# Sheet1.net
KiCad netlist of a schematic drawn in Altium Designer
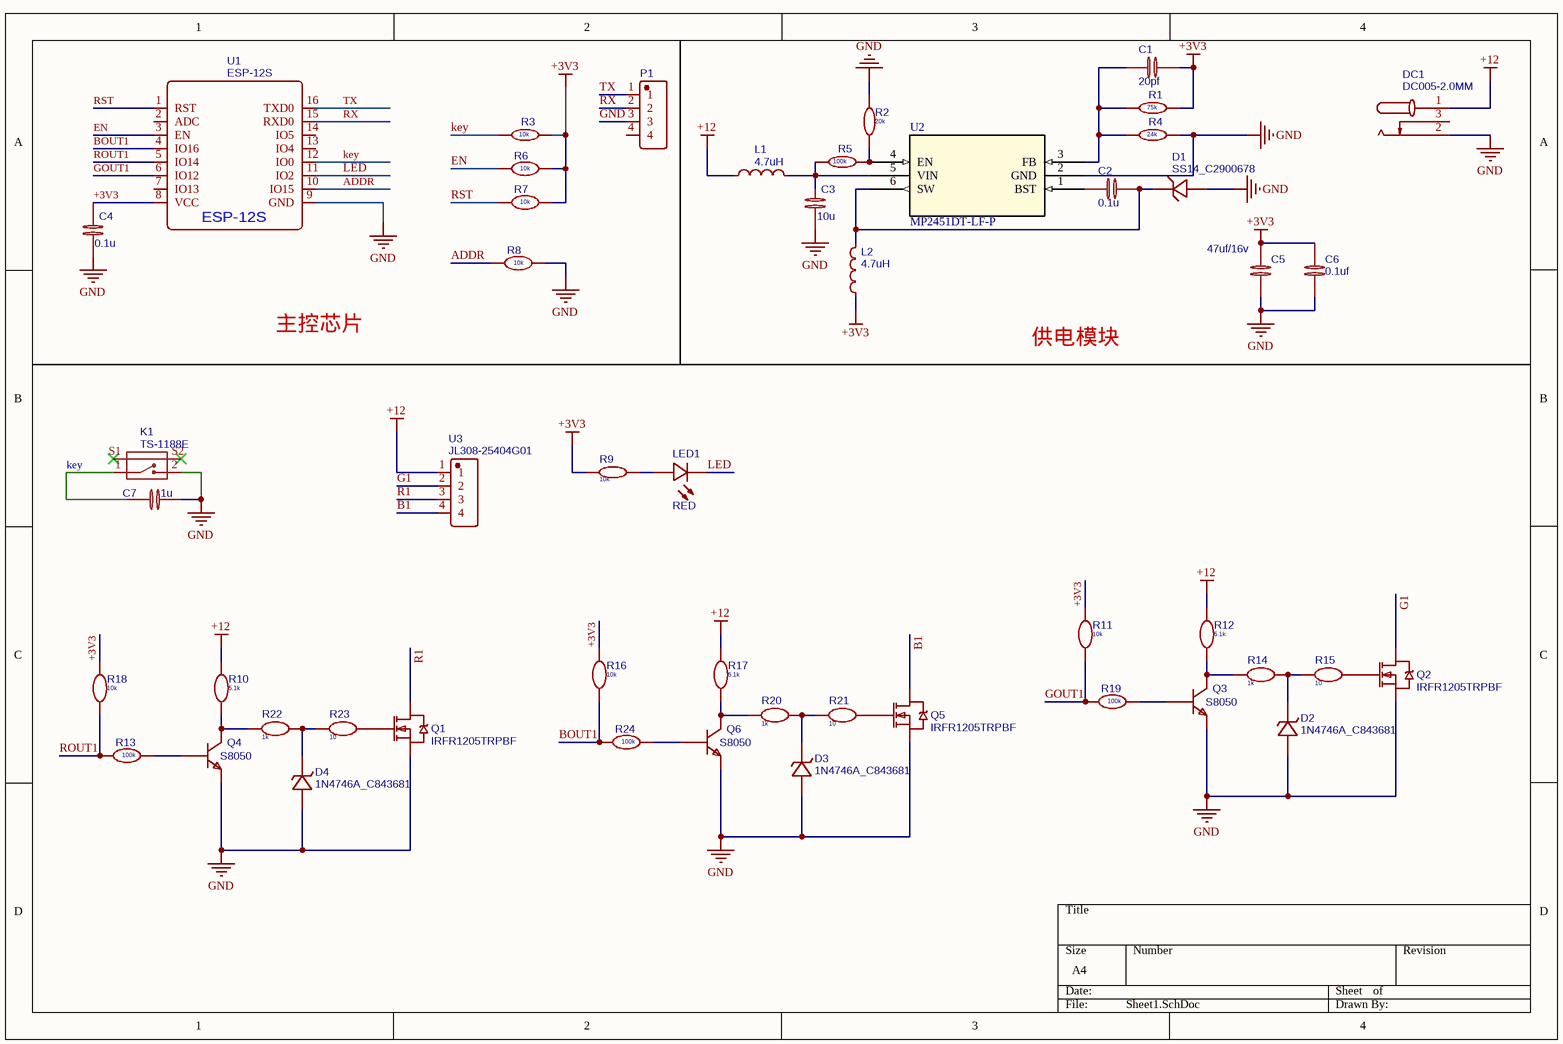
[diagram p0: Sheet1.SchDoc]

(export (version "E")
  (design (tool "Eeschema 10.0.6"))
  (components
    (comp (ref "C1")
      (value "20pf")
      (footprint "C0603")
      (fields (field (name "CONTRIBUTOR") "LCEDA_Lib"))
      (libsource (lib "altium-import") (part "root_0_0.1u_"))
    )
    (comp (ref "C2")
      (value "0.1u")
      (footprint "C0603")
      (fields (field (name "CONTRIBUTOR") "LCEDA_Lib"))
      (libsource (lib "altium-import") (part "root_0_0.1u_"))
    )
    (comp (ref "C3")
      (value "10u")
      (footprint "C0603")
      (fields (field (name "CONTRIBUTOR") "LCEDA_Lib"))
      (libsource (lib "altium-import") (part "root_1_0.1u_"))
    )
    (comp (ref "C4")
      (value "0.1u")
      (footprint "C0603")
      (fields (field (name "CONTRIBUTOR") "LCEDA_Lib"))
      (libsource (lib "altium-import") (part "root_1_0.1u_"))
    )
    (comp (ref "C5")
      (value "47uf/16v")
      (footprint "C0603")
      (fields (field (name "CONTRIBUTOR") "LCEDA_Lib"))
      (libsource (lib "altium-import") (part "root_1_0.1u_"))
    )
    (comp (ref "C6")
      (value "0.1uf")
      (footprint "C0603")
      (fields (field (name "CONTRIBUTOR") "LCEDA_Lib"))
      (libsource (lib "altium-import") (part "root_1_0.1u_"))
    )
    (comp (ref "C7")
      (value "1u")
      (footprint "C0603")
      (fields (field (name "CONTRIBUTOR") "LCEDA_Lib"))
      (libsource (lib "altium-import") (part "root_2_1u_"))
    )
    (comp (ref "D1")
      (value "SS14_C2900678")
      (footprint "SMA_L4.3-W2.5-LS5.0-RD-1")
      (fields
        (field (name "BOM_SUPPLIER PART") "C2900678")
        (field (name "BOM_MANUFACTURER PART") "SS14")
        (field (name "CONTRIBUTOR") "LCSC")
      )
      (libsource (lib "altium-import") (part "root_0_SS14_C2900678_"))
    )
    (comp (ref "D2")
      (value "1N4746A_C843681")
      (footprint "DO-41_BD2.8-L4.2-P8.00-D0.7-FD")
      (fields
        (field (name "BOM_SUPPLIER PART") "C843681")
        (field (name "BOM_MANUFACTURER PART") "1N4746A")
        (field (name "CONTRIBUTOR") "LCSC")
      )
      (libsource (lib "altium-import") (part "root_3_1N4746A_C843681_"))
    )
    (comp (ref "D3")
      (value "1N4746A_C843681")
      (footprint "DO-41_BD2.8-L4.2-P8.00-D0.7-FD")
      (fields
        (field (name "BOM_SUPPLIER PART") "C843681")
        (field (name "BOM_MANUFACTURER PART") "1N4746A")
        (field (name "CONTRIBUTOR") "LCSC")
      )
      (libsource (lib "altium-import") (part "root_3_1N4746A_C843681_"))
    )
    (comp (ref "D4")
      (value "1N4746A_C843681")
      (footprint "DO-41_BD2.8-L4.2-P8.00-D0.7-FD")
      (fields
        (field (name "BOM_SUPPLIER PART") "C843681")
        (field (name "BOM_MANUFACTURER PART") "1N4746A")
        (field (name "CONTRIBUTOR") "LCSC")
      )
      (libsource (lib "altium-import") (part "root_3_1N4746A_C843681_"))
    )
    (comp (ref "DC1")
      (value "DC005-2.0MM")
      (footprint "DC-IN-TH_DC005-T20")
      (fields (field (name "BOM_SUPPLIER PART") "C111567"))
      (libsource (lib "altium-import") (part "root_0_DC005-2.0MM_"))
    )
    (comp (ref "K1")
      (value "TS-1188E")
      (footprint "SMD SWITCH 7X3.6X2.7")
      (fields
        (field (name "BOM_MANUFACTURER PART") "3*6*3.5 Side press  High temperature")
        (field (name "BOM_SUPPLIER PART") "C37327")
      )
      (libsource (lib "altium-import") (part "root_0_TS-1188E_"))
    )
    (comp (ref "L1")
      (value "4.7uH")
      (footprint "IND-SMD_L7.3-W6.6_MHCI06030")
      (fields
        (field (name "BOM_MANUFACTURER PART") "SMMS0630-4R7M")
        (field (name "BOM_SUPPLIER PART") "C128688")
      )
      (libsource (lib "altium-import") (part "root_0_4.7uH_"))
    )
    (comp (ref "L2")
      (value "4.7uH")
      (footprint "IND-SMD_L7.3-W6.6_MHCI06030")
      (fields
        (field (name "BOM_MANUFACTURER PART") "SMMS0630-4R7M")
        (field (name "BOM_SUPPLIER PART") "C128688")
      )
      (libsource (lib "altium-import") (part "root_1_4.7uH_"))
    )
    (comp (ref "LED1")
      (value "RED")
      (footprint "LED0603-R-RD")
      (fields
        (field (name "BOM_SUPPLIER PART") "C375444")
        (field (name "BOM_MANUFACTURER PART") "E6C0603URAC1UDA")
        (field (name "CONTRIBUTOR") "LCSC")
      )
      (libsource (lib "altium-import") (part "root_2_RED_"))
    )
    (comp (ref "P1")
      (value "~")
      (footprint "HDR-TH_4P-P2.54-V-M")
      (fields
        (field (name "BOM_SUPPLIER PART") "C2905435")
        (field (name "BOM_MANUFACTURER PART") "KH-2.54PH180-1X4P-L11.5")
        (field (name "CONTRIBUTOR") "LCSC")
      )
      (libsource (lib "altium-import") (part "root_0_KH-2.54PH180-1X4P-L11.5_"))
    )
    (comp (ref "Q1")
      (value "IRFR1205TRPBF")
      (footprint "TO-252-2_L6.5-W6.1-P4.58-LS10.0-TR")
      (fields (field (name "BOM_SUPPLIER PART") "C81467"))
      (libsource (lib "altium-import") (part "root_0_IRFR1205TRPBF_"))
    )
    (comp (ref "Q2")
      (value "IRFR1205TRPBF")
      (footprint "TO-252-2_L6.5-W6.1-P4.58-LS10.0-TR")
      (fields (field (name "BOM_SUPPLIER PART") "C81467"))
      (libsource (lib "altium-import") (part "root_0_IRFR1205TRPBF_"))
    )
    (comp (ref "Q3")
      (value "S8050")
      (footprint "SOT-23(SOT-23-3)")
      (fields (field (name "BOM_SUPPLIER PART") "C139514") (field (name "CONTRIBUTOR") "LCSC"))
      (libsource (lib "altium-import") (part "root_2_S8050_"))
    )
    (comp (ref "Q4")
      (value "S8050")
      (footprint "SOT-23(SOT-23-3)")
      (fields (field (name "BOM_SUPPLIER PART") "C139514") (field (name "CONTRIBUTOR") "LCSC"))
      (libsource (lib "altium-import") (part "root_2_S8050_"))
    )
    (comp (ref "Q5")
      (value "IRFR1205TRPBF")
      (footprint "TO-252-2_L6.5-W6.1-P4.58-LS10.0-TR")
      (fields (field (name "BOM_SUPPLIER PART") "C81467"))
      (libsource (lib "altium-import") (part "root_0_IRFR1205TRPBF_"))
    )
    (comp (ref "Q6")
      (value "S8050")
      (footprint "SOT-23(SOT-23-3)")
      (fields (field (name "BOM_SUPPLIER PART") "C139514") (field (name "CONTRIBUTOR") "LCSC"))
      (libsource (lib "altium-import") (part "root_2_S8050_"))
    )
    (comp (ref "R1")
      (value "75k")
      (footprint "R0603")
      (fields
        (field (name "BOM_MANUFACTURER PART") "CRCW060310K0JNEA")
        (field (name "BOM_SUPPLIER PART") "C169103")
      )
      (libsource (lib "altium-import") (part "root_0_10k_"))
    )
    (comp (ref "R2")
      (value "20k")
      (footprint "R0603")
      (fields
        (field (name "BOM_MANUFACTURER PART") "CRCW060310K0JNEA")
        (field (name "BOM_SUPPLIER PART") "C169103")
      )
      (libsource (lib "altium-import") (part "root_1_10k_"))
    )
    (comp (ref "R3")
      (value "10k")
      (footprint "R0603")
      (fields
        (field (name "BOM_MANUFACTURER PART") "CRCW060310K0JNEA")
        (field (name "BOM_SUPPLIER PART") "C169103")
      )
      (libsource (lib "altium-import") (part "root_0_10k_"))
    )
    (comp (ref "R4")
      (value "24k")
      (footprint "R0603")
      (fields
        (field (name "BOM_MANUFACTURER PART") "CRCW060310K0JNEA")
        (field (name "BOM_SUPPLIER PART") "C169103")
      )
      (libsource (lib "altium-import") (part "root_0_10k_"))
    )
    (comp (ref "R5")
      (value "100k")
      (footprint "R0603")
      (fields
        (field (name "BOM_MANUFACTURER PART") "CRCW060310K0JNEA")
        (field (name "BOM_SUPPLIER PART") "C169103")
      )
      (libsource (lib "altium-import") (part "root_0_10k_"))
    )
    (comp (ref "R6")
      (value "10k")
      (footprint "R0603")
      (fields (field (name "CONTRIBUTOR") "LCEDA_Lib"))
      (libsource (lib "altium-import") (part "root_0_NC_"))
    )
    (comp (ref "R7")
      (value "10k")
      (footprint "R0603")
      (fields (field (name "CONTRIBUTOR") "LCEDA_Lib"))
      (libsource (lib "altium-import") (part "root_0_NC_"))
    )
    (comp (ref "R8")
      (value "10k")
      (footprint "R0603")
      (fields (field (name "CONTRIBUTOR") "LCEDA_Lib"))
      (libsource (lib "altium-import") (part "root_0_NC_"))
    )
    (comp (ref "R9")
      (value "10k")
      (footprint "R0603")
      (fields
        (field (name "BOM_MANUFACTURER PART") "CRCW060310K0JNEA")
        (field (name "BOM_SUPPLIER PART") "C169103")
      )
      (libsource (lib "altium-import") (part "root_2_10k_"))
    )
    (comp (ref "R10")
      (value "5.1k")
      (footprint "R0603")
      (fields (field (name "CONTRIBUTOR") "LCEDA_Lib"))
      (libsource (lib "altium-import") (part "root_1_NC_"))
    )
    (comp (ref "R11")
      (value "10k")
      (footprint "R0603")
      (fields (field (name "CONTRIBUTOR") "LCEDA_Lib"))
      (libsource (lib "altium-import") (part "root_1_NC_"))
    )
    (comp (ref "R12")
      (value "5.1k")
      (footprint "R0603")
      (fields (field (name "CONTRIBUTOR") "LCEDA_Lib"))
      (libsource (lib "altium-import") (part "root_1_NC_"))
    )
    (comp (ref "R13")
      (value "100k")
      (footprint "R0603")
      (fields (field (name "CONTRIBUTOR") "LCEDA_Lib"))
      (libsource (lib "altium-import") (part "root_0_NC_"))
    )
    (comp (ref "R14")
      (value "1k")
      (footprint "R0603")
      (fields (field (name "CONTRIBUTOR") "LCEDA_Lib"))
      (libsource (lib "altium-import") (part "root_2_NC_"))
    )
    (comp (ref "R15")
      (value "10")
      (footprint "R0603")
      (fields (field (name "CONTRIBUTOR") "LCEDA_Lib"))
      (libsource (lib "altium-import") (part "root_2_NC_"))
    )
    (comp (ref "R16")
      (value "10k")
      (footprint "R0603")
      (fields (field (name "CONTRIBUTOR") "LCEDA_Lib"))
      (libsource (lib "altium-import") (part "root_1_NC_"))
    )
    (comp (ref "R17")
      (value "5.1k")
      (footprint "R0603")
      (fields (field (name "CONTRIBUTOR") "LCEDA_Lib"))
      (libsource (lib "altium-import") (part "root_1_NC_"))
    )
    (comp (ref "R18")
      (value "10k")
      (footprint "R0603")
      (fields (field (name "CONTRIBUTOR") "LCEDA_Lib"))
      (libsource (lib "altium-import") (part "root_1_NC_"))
    )
    (comp (ref "R19")
      (value "100k")
      (footprint "R0603")
      (fields (field (name "CONTRIBUTOR") "LCEDA_Lib"))
      (libsource (lib "altium-import") (part "root_0_NC_"))
    )
    (comp (ref "R20")
      (value "1k")
      (footprint "R0603")
      (fields (field (name "CONTRIBUTOR") "LCEDA_Lib"))
      (libsource (lib "altium-import") (part "root_2_NC_"))
    )
    (comp (ref "R21")
      (value "10")
      (footprint "R0603")
      (fields (field (name "CONTRIBUTOR") "LCEDA_Lib"))
      (libsource (lib "altium-import") (part "root_2_NC_"))
    )
    (comp (ref "R22")
      (value "1k")
      (footprint "R0603")
      (fields (field (name "CONTRIBUTOR") "LCEDA_Lib"))
      (libsource (lib "altium-import") (part "root_2_NC_"))
    )
    (comp (ref "R23")
      (value "10")
      (footprint "R0603")
      (fields (field (name "CONTRIBUTOR") "LCEDA_Lib"))
      (libsource (lib "altium-import") (part "root_2_NC_"))
    )
    (comp (ref "R24")
      (value "100k")
      (footprint "R0603")
      (fields (field (name "CONTRIBUTOR") "LCEDA_Lib"))
      (libsource (lib "altium-import") (part "root_0_NC_"))
    )
    (comp (ref "U1")
      (value "ESP-12S")
      (footprint "WIFIM-SMD_ESP-12F-ESP8266MOD")
      (fields (field (name "BOM_SUPPLIER PART") "C82898") (field (name "CONTRIBUTOR") "HalfSweet"))
      (libsource (lib "altium-import") (part "root_0_ESP-12S_"))
    )
    (comp (ref "U2")
      (value "MP2451DT-LF-P")
      (footprint "SOT23-6_MPS")
      (description "No Description Available")
      (fields (field (name "COPYRIGHT") "Copyright (C) 2022 Ultra Librarian. All rights reserved."))
      (libsource (lib "MP2451DT-LF-P") (part "MP2451DT-LF-P"))
    )
    (comp (ref "U3")
      (value "JL308-25404G01")
      (footprint "CONN-TH_4P-P2.54_JILN_JL308-25404G01")
      (fields (field (name "BOM_SUPPLIER PART") "C2922599") (field (name "CONTRIBUTOR") "LCSC"))
      (libsource (lib "altium-import") (part "root_0_JL308-25404G01_"))
    )
  )
  (nets
    (net (code "1") (name "+3V3") (class "Default")
      (node (ref "C1") (pin "2") (pinfunction "2_2") (pintype "passive"))
      (node (ref "C4") (pin "2") (pinfunction "2_2") (pintype "passive"))
      (node (ref "C5") (pin "2") (pinfunction "2_2") (pintype "passive"))
      (node (ref "C6") (pin "2") (pinfunction "2_2") (pintype "passive"))
      (node (ref "L2") (pin "1") (pinfunction "1_1") (pintype "passive"))
      (node (ref "R1") (pin "1") (pinfunction "1_1") (pintype "passive"))
      (node (ref "R11") (pin "2") (pinfunction "2_2") (pintype "passive"))
      (node (ref "R16") (pin "2") (pinfunction "2_2") (pintype "passive"))
      (node (ref "R18") (pin "2") (pinfunction "2_2") (pintype "passive"))
      (node (ref "R3") (pin "1") (pinfunction "1_1") (pintype "passive"))
      (node (ref "R6") (pin "2") (pinfunction "2_2") (pintype "passive"))
      (node (ref "R7") (pin "2") (pinfunction "2_2") (pintype "passive"))
      (node (ref "R9") (pin "1") (pinfunction "1_1") (pintype "passive"))
      (node (ref "U1") (pin "8") (pinfunction "VCC_8") (pintype "passive"))
    )
    (net (code "2") (name "+12") (class "Default")
      (node (ref "DC1") (pin "1") (pinfunction "1_1") (pintype "passive"))
      (node (ref "L1") (pin "1") (pinfunction "1_1") (pintype "passive"))
      (node (ref "R10") (pin "2") (pinfunction "2_2") (pintype "passive"))
      (node (ref "R12") (pin "2") (pinfunction "2_2") (pintype "passive"))
      (node (ref "R17") (pin "2") (pinfunction "2_2") (pintype "passive"))
      (node (ref "U3") (pin "1") (pinfunction "1_1") (pintype "passive"))
    )
    (net (code "3") (name "/ADDR") (class "Default")
      (node (ref "R8") (pin "1") (pinfunction "1_1") (pintype "passive"))
      (node (ref "U1") (pin "10") (pinfunction "IO15_10") (pintype "passive"))
    )
    (net (code "4") (name "/B1") (class "Default")
      (node (ref "Q5") (pin "4") (pinfunction "D_4") (pintype "passive"))
      (node (ref "U3") (pin "4") (pinfunction "4_4") (pintype "passive"))
    )
    (net (code "5") (name "/BOUT1") (class "Default")
      (node (ref "R16") (pin "1") (pinfunction "1_1") (pintype "passive"))
      (node (ref "R24") (pin "1") (pinfunction "1_1") (pintype "passive"))
      (node (ref "U1") (pin "4") (pinfunction "IO16_4") (pintype "passive"))
    )
    (net (code "6") (name "/EN") (class "Default")
      (node (ref "R6") (pin "1") (pinfunction "1_1") (pintype "passive"))
      (node (ref "U1") (pin "3") (pinfunction "EN_3") (pintype "passive"))
    )
    (net (code "7") (name "/G1") (class "Default")
      (node (ref "Q2") (pin "4") (pinfunction "D_4") (pintype "passive"))
      (node (ref "U3") (pin "2") (pinfunction "2_2") (pintype "passive"))
    )
    (net (code "8") (name "/GOUT1") (class "Default")
      (node (ref "R11") (pin "1") (pinfunction "1_1") (pintype "passive"))
      (node (ref "R19") (pin "1") (pinfunction "1_1") (pintype "passive"))
      (node (ref "U1") (pin "6") (pinfunction "IO12_6") (pintype "passive"))
    )
    (net (code "9") (name "/LED") (class "Default")
      (node (ref "LED1") (pin "2") (pinfunction "-_2") (pintype "passive"))
      (node (ref "U1") (pin "11") (pinfunction "IO2_11") (pintype "passive"))
    )
    (net (code "10") (name "/R1") (class "Default")
      (node (ref "Q1") (pin "4") (pinfunction "D_4") (pintype "passive"))
      (node (ref "U3") (pin "3") (pinfunction "3_3") (pintype "passive"))
    )
    (net (code "11") (name "/ROUT1") (class "Default")
      (node (ref "R13") (pin "1") (pinfunction "1_1") (pintype "passive"))
      (node (ref "R18") (pin "1") (pinfunction "1_1") (pintype "passive"))
      (node (ref "U1") (pin "5") (pinfunction "IO14_5") (pintype "passive"))
    )
    (net (code "12") (name "/RST") (class "Default")
      (node (ref "R7") (pin "1") (pinfunction "1_1") (pintype "passive"))
      (node (ref "U1") (pin "1") (pinfunction "RST_1") (pintype "passive"))
    )
    (net (code "13") (name "/RX") (class "Default")
      (node (ref "P1") (pin "2") (pinfunction "2_2") (pintype "passive"))
      (node (ref "U1") (pin "15") (pinfunction "RXD0_15") (pintype "passive"))
    )
    (net (code "14") (name "/TX") (class "Default")
      (node (ref "P1") (pin "1") (pinfunction "1_1") (pintype "passive"))
      (node (ref "U1") (pin "16") (pinfunction "TXD0_16") (pintype "passive"))
    )
    (net (code "15") (name "/key") (class "Default")
      (node (ref "C7") (pin "2") (pinfunction "2_2") (pintype "passive"))
      (node (ref "K1") (pin "1") (pinfunction "1_1") (pintype "passive"))
      (node (ref "R3") (pin "2") (pinfunction "2_2") (pintype "passive"))
      (node (ref "U1") (pin "12") (pinfunction "IO0_12") (pintype "passive"))
    )
    (net (code "16") (name "GND") (class "Default")
      (node (ref "C3") (pin "1") (pinfunction "1_1") (pintype "passive"))
      (node (ref "C4") (pin "1") (pinfunction "1_1") (pintype "passive"))
      (node (ref "C5") (pin "1") (pinfunction "1_1") (pintype "passive"))
      (node (ref "C6") (pin "1") (pinfunction "1_1") (pintype "passive"))
      (node (ref "C7") (pin "1") (pinfunction "1_1") (pintype "passive"))
      (node (ref "D1") (pin "2") (pinfunction "A_2") (pintype "passive"))
      (node (ref "D2") (pin "2") (pinfunction "A_2") (pintype "passive"))
      (node (ref "D3") (pin "2") (pinfunction "A_2") (pintype "passive"))
      (node (ref "D4") (pin "2") (pinfunction "A_2") (pintype "passive"))
      (node (ref "DC1") (pin "2") (pinfunction "2_2") (pintype "passive"))
      (node (ref "K1") (pin "2") (pinfunction "2_2") (pintype "passive"))
      (node (ref "P1") (pin "3") (pinfunction "3_3") (pintype "passive"))
      (node (ref "Q1") (pin "3") (pinfunction "S_3") (pintype "passive"))
      (node (ref "Q2") (pin "3") (pinfunction "S_3") (pintype "passive"))
      (node (ref "Q3") (pin "2") (pinfunction "E_2") (pintype "passive"))
      (node (ref "Q4") (pin "2") (pinfunction "E_2") (pintype "passive"))
      (node (ref "Q5") (pin "3") (pinfunction "S_3") (pintype "passive"))
      (node (ref "Q6") (pin "2") (pinfunction "E_2") (pintype "passive"))
      (node (ref "R2") (pin "1") (pinfunction "1_1") (pintype "passive"))
      (node (ref "R4") (pin "1") (pinfunction "1_1") (pintype "passive"))
      (node (ref "R8") (pin "2") (pinfunction "2_2") (pintype "passive"))
      (node (ref "U1") (pin "9") (pinfunction "GND_9") (pintype "passive"))
      (node (ref "U2") (pin "2") (pinfunction "GND_2") (pintype "passive"))
    )
    (net (code "17") (name "Net-(D1-C)") (class "Default")
      (node (ref "C2") (pin "2") (pinfunction "2_2") (pintype "passive"))
      (node (ref "D1") (pin "1") (pinfunction "C_1") (pintype "passive"))
      (node (ref "L2") (pin "2") (pinfunction "2_2") (pintype "passive"))
      (node (ref "U2") (pin "6") (pinfunction "SW_6") (pintype "output"))
    )
    (net (code "18") (name "Net-(D2-K)") (class "Default")
      (node (ref "D2") (pin "1") (pinfunction "K_1") (pintype "passive"))
      (node (ref "R14") (pin "1") (pinfunction "1_1") (pintype "passive"))
      (node (ref "R15") (pin "2") (pinfunction "2_2") (pintype "passive"))
    )
    (net (code "19") (name "Net-(D3-K)") (class "Default")
      (node (ref "D3") (pin "1") (pinfunction "K_1") (pintype "passive"))
      (node (ref "R20") (pin "1") (pinfunction "1_1") (pintype "passive"))
      (node (ref "R21") (pin "2") (pinfunction "2_2") (pintype "passive"))
    )
    (net (code "20") (name "Net-(D4-K)") (class "Default")
      (node (ref "D4") (pin "1") (pinfunction "K_1") (pintype "passive"))
      (node (ref "R22") (pin "1") (pinfunction "1_1") (pintype "passive"))
      (node (ref "R23") (pin "2") (pinfunction "2_2") (pintype "passive"))
    )
    (net (code "21") (name "Net-(LED1-+)") (class "Default")
      (node (ref "LED1") (pin "1") (pinfunction "+_1") (pintype "passive"))
      (node (ref "R9") (pin "2") (pinfunction "2_2") (pintype "passive"))
    )
    (net (code "22") (name "Net-(Q1-G)") (class "Default")
      (node (ref "Q1") (pin "1") (pinfunction "G_1") (pintype "passive"))
      (node (ref "R23") (pin "1") (pinfunction "1_1") (pintype "passive"))
    )
    (net (code "23") (name "Net-(Q2-G)") (class "Default")
      (node (ref "Q2") (pin "1") (pinfunction "G_1") (pintype "passive"))
      (node (ref "R15") (pin "1") (pinfunction "1_1") (pintype "passive"))
    )
    (net (code "24") (name "Net-(Q3-B)") (class "Default")
      (node (ref "Q3") (pin "1") (pinfunction "B_1") (pintype "passive"))
      (node (ref "R19") (pin "2") (pinfunction "2_2") (pintype "passive"))
    )
    (net (code "25") (name "Net-(Q3-C)") (class "Default")
      (node (ref "Q3") (pin "3") (pinfunction "C_3") (pintype "passive"))
      (node (ref "R12") (pin "1") (pinfunction "1_1") (pintype "passive"))
      (node (ref "R14") (pin "2") (pinfunction "2_2") (pintype "passive"))
    )
    (net (code "26") (name "Net-(Q4-B)") (class "Default")
      (node (ref "Q4") (pin "1") (pinfunction "B_1") (pintype "passive"))
      (node (ref "R13") (pin "2") (pinfunction "2_2") (pintype "passive"))
    )
    (net (code "27") (name "Net-(Q4-C)") (class "Default")
      (node (ref "Q4") (pin "3") (pinfunction "C_3") (pintype "passive"))
      (node (ref "R10") (pin "1") (pinfunction "1_1") (pintype "passive"))
      (node (ref "R22") (pin "2") (pinfunction "2_2") (pintype "passive"))
    )
    (net (code "28") (name "Net-(Q5-G)") (class "Default")
      (node (ref "Q5") (pin "1") (pinfunction "G_1") (pintype "passive"))
      (node (ref "R21") (pin "1") (pinfunction "1_1") (pintype "passive"))
    )
    (net (code "29") (name "Net-(Q6-B)") (class "Default")
      (node (ref "Q6") (pin "1") (pinfunction "B_1") (pintype "passive"))
      (node (ref "R24") (pin "2") (pinfunction "2_2") (pintype "passive"))
    )
    (net (code "30") (name "Net-(Q6-C)") (class "Default")
      (node (ref "Q6") (pin "3") (pinfunction "C_3") (pintype "passive"))
      (node (ref "R17") (pin "1") (pinfunction "1_1") (pintype "passive"))
      (node (ref "R20") (pin "2") (pinfunction "2_2") (pintype "passive"))
    )
    (net (code "31") (name "Net-(U2-BST)") (class "Default")
      (node (ref "C2") (pin "1") (pinfunction "1_1") (pintype "passive"))
      (node (ref "U2") (pin "1") (pinfunction "BST_1") (pintype "input"))
    )
    (net (code "32") (name "Net-(U2-EN)") (class "Default")
      (node (ref "R2") (pin "2") (pinfunction "2_2") (pintype "passive"))
      (node (ref "R5") (pin "1") (pinfunction "1_1") (pintype "passive"))
      (node (ref "U2") (pin "4") (pinfunction "EN_4") (pintype "input"))
    )
    (net (code "33") (name "Net-(U2-FB)") (class "Default")
      (node (ref "C1") (pin "1") (pinfunction "1_1") (pintype "passive"))
      (node (ref "R1") (pin "2") (pinfunction "2_2") (pintype "passive"))
      (node (ref "R4") (pin "2") (pinfunction "2_2") (pintype "passive"))
      (node (ref "U2") (pin "3") (pinfunction "FB_3") (pintype "input"))
    )
    (net (code "34") (name "Net-(U2-VIN)") (class "Default")
      (node (ref "C3") (pin "2") (pinfunction "2_2") (pintype "passive"))
      (node (ref "L1") (pin "2") (pinfunction "2_2") (pintype "passive"))
      (node (ref "R5") (pin "2") (pinfunction "2_2") (pintype "passive"))
      (node (ref "U2") (pin "5") (pinfunction "VIN_5") (pintype "power_in"))
    )
    (net (code "35") (name "unconnected-(DC1-Pad3)") (class "Default")
      (node (ref "DC1") (pin "3") (pinfunction "3_3") (pintype "passive"))
    )
    (net (code "36") (name "unconnected-(K1-PadS1)") (class "Default")
      (node (ref "K1") (pin "S1") (pinfunction "S1_S1") (pintype "passive+no_connect"))
    )
    (net (code "37") (name "unconnected-(K1-PadS2)") (class "Default")
      (node (ref "K1") (pin "S2") (pinfunction "S2_S2") (pintype "passive+no_connect"))
    )
    (net (code "38") (name "unconnected-(P1-Pad4)") (class "Default")
      (node (ref "P1") (pin "4") (pinfunction "4_4") (pintype "passive"))
    )
    (net (code "39") (name "unconnected-(U1-ADC-Pad2)") (class "Default")
      (node (ref "U1") (pin "2") (pinfunction "ADC_2") (pintype "passive"))
    )
    (net (code "40") (name "unconnected-(U1-IO4-Pad13)") (class "Default")
      (node (ref "U1") (pin "13") (pinfunction "IO4_13") (pintype "passive"))
    )
    (net (code "41") (name "unconnected-(U1-IO5-Pad14)") (class "Default")
      (node (ref "U1") (pin "14") (pinfunction "IO5_14") (pintype "passive"))
    )
    (net (code "42") (name "unconnected-(U1-IO13-Pad7)") (class "Default")
      (node (ref "U1") (pin "7") (pinfunction "IO13_7") (pintype "passive"))
    )
  )
)
